# IO_BOTTOM_PCB_BOARD.net
KiCad netlist of a schematic drawn in EAGLE
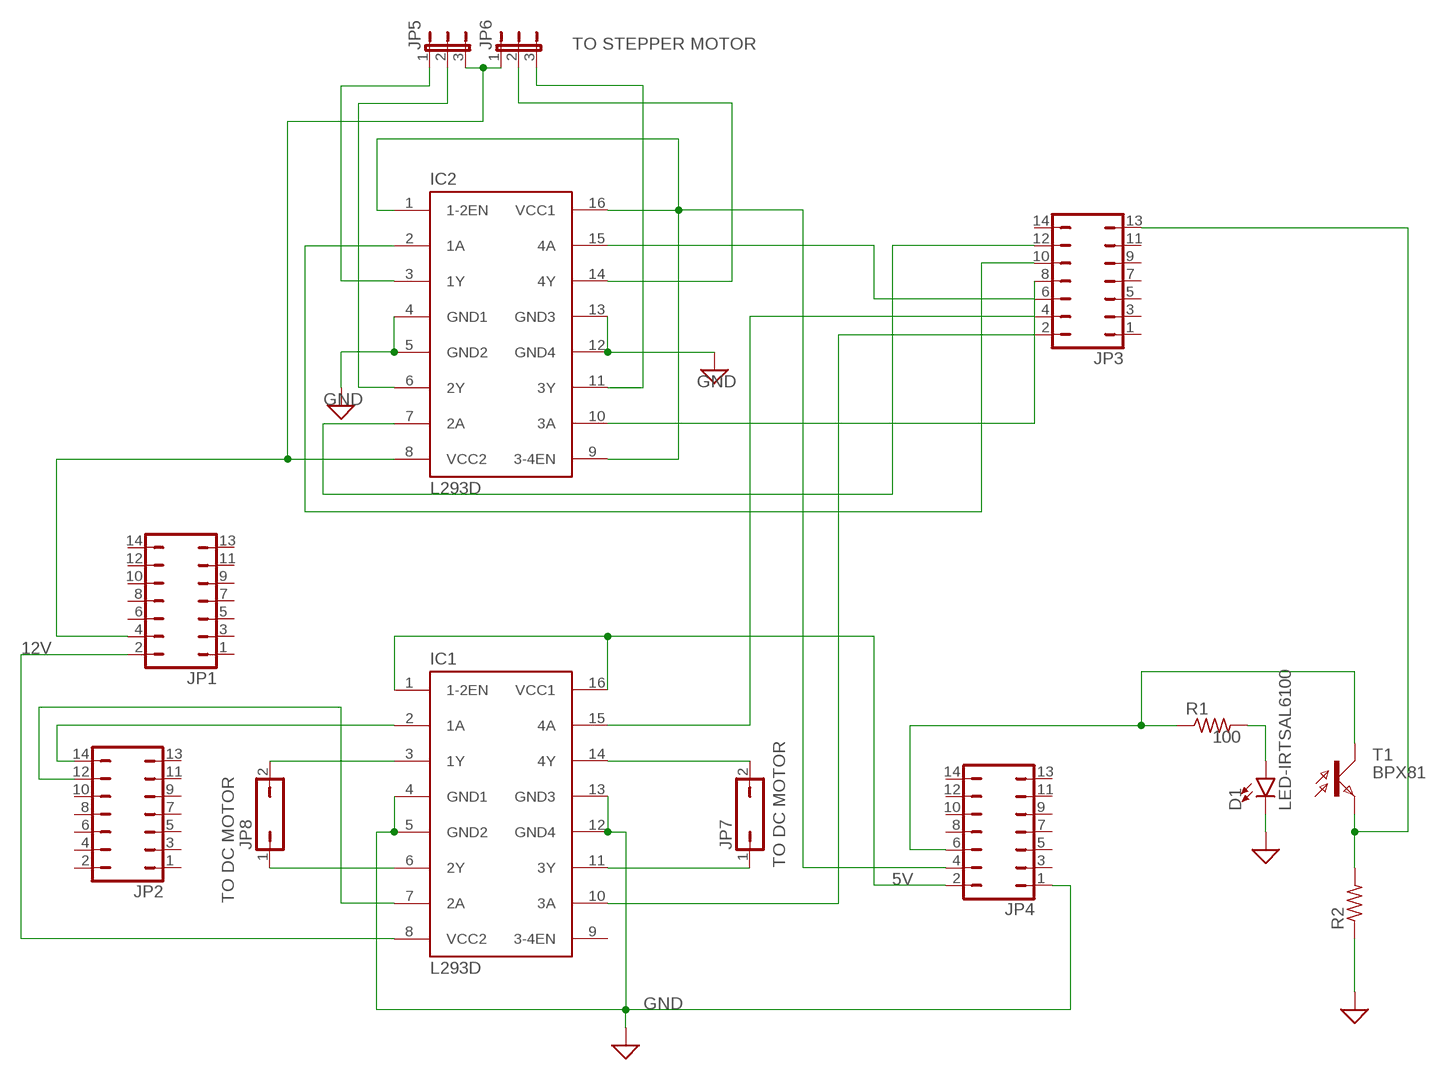
[diagram p0: schematic, sheet 1]

(export (version "E")
  (design (tool "Eeschema 10.0.6"))
  (components
    (comp (ref "D1")
      (value "LED-IRTSAL6100")
      (footprint "eagle-import:LED_5MM")
      (libsource (lib "eagle-import") (part "LED-IRTSAL6100"))
    )
    (comp (ref "IC1")
      (value "L293D")
      (footprint "eagle-import:DIL16")
      (libsource (lib "eagle-import") (part "L293D"))
    )
    (comp (ref "IC2")
      (value "L293D")
      (footprint "eagle-import:DIL16")
      (libsource (lib "eagle-import") (part "L293D"))
    )
    (comp (ref "JP1")
      (value "JP7Q")
      (footprint "eagle-import:JP7Q")
      (libsource (lib "eagle-import") (part "JP7Q"))
    )
    (comp (ref "JP2")
      (value "JP7Q")
      (footprint "eagle-import:JP7Q")
      (libsource (lib "eagle-import") (part "JP7Q"))
    )
    (comp (ref "JP3")
      (value "JP7Q")
      (footprint "eagle-import:JP7Q")
      (libsource (lib "eagle-import") (part "JP7Q"))
    )
    (comp (ref "JP4")
      (value "JP7Q")
      (footprint "eagle-import:JP7Q")
      (libsource (lib "eagle-import") (part "JP7Q"))
    )
    (comp (ref "JP5")
      (value "JP2E")
      (footprint "eagle-import:JP2")
      (libsource (lib "eagle-import") (part "JP2E"))
    )
    (comp (ref "JP6")
      (value "JP2E")
      (footprint "eagle-import:JP2")
      (libsource (lib "eagle-import") (part "JP2E"))
    )
    (comp (ref "JP7")
      (value "JP1Q")
      (footprint "eagle-import:JP1")
      (libsource (lib "eagle-import") (part "JP1Q"))
    )
    (comp (ref "JP8")
      (value "JP1Q")
      (footprint "eagle-import:JP1")
      (libsource (lib "eagle-import") (part "JP1Q"))
    )
    (comp (ref "R1")
      (value "R-US_0204/2V")
      (footprint "eagle-import:0204V")
      (libsource (lib "eagle-import") (part "R-US_0204/2V"))
    )
    (comp (ref "R2")
      (value "R-US_0204/2V")
      (footprint "eagle-import:0204V")
      (libsource (lib "eagle-import") (part "R-US_0204/2V"))
    )
    (comp (ref "T1")
      (value "BPX81")
      (footprint "eagle-import:BPX81")
      (libsource (lib "eagle-import") (part "BPX81"))
    )
  )
  (nets
    (net (code "1") (name "/5V") (class "Default")
      (node (ref "IC1") (pin "8") (pinfunction "VCC2_8") (pintype "power_in"))
      (node (ref "JP1") (pin "2") (pinfunction "2_2") (pintype "passive"))
    )
    (net (code "2") (name "Net-(D1-PadA)") (class "Default")
      (node (ref "D1") (pin "A") (pinfunction "A_A") (pintype "passive"))
      (node (ref "R1") (pin "2") (pinfunction "2_2") (pintype "passive"))
    )
    (net (code "3") (name "Net-(IC1-1-2EN)") (class "Default")
      (node (ref "IC1") (pin "1") (pinfunction "1-2EN_1") (pintype "input"))
      (node (ref "IC1") (pin "16") (pinfunction "VCC1_16") (pintype "power_in"))
      (node (ref "JP4") (pin "2") (pinfunction "2_2") (pintype "passive"))
    )
    (net (code "4") (name "Net-(IC1-1A)") (class "Default")
      (node (ref "IC1") (pin "2") (pinfunction "1A_2") (pintype "input"))
      (node (ref "JP2") (pin "14") (pinfunction "14_14") (pintype "passive"))
    )
    (net (code "5") (name "Net-(IC1-1Y)") (class "Default")
      (node (ref "IC1") (pin "3") (pinfunction "1Y_3") (pintype "output"))
      (node (ref "JP8") (pin "2") (pinfunction "2_2") (pintype "passive"))
    )
    (net (code "6") (name "Net-(IC1-2A)") (class "Default")
      (node (ref "IC1") (pin "7") (pinfunction "2A_7") (pintype "input"))
      (node (ref "JP2") (pin "12") (pinfunction "12_12") (pintype "passive"))
    )
    (net (code "7") (name "Net-(IC1-2Y)") (class "Default")
      (node (ref "IC1") (pin "6") (pinfunction "2Y_6") (pintype "output"))
      (node (ref "JP8") (pin "1") (pinfunction "1_1") (pintype "passive"))
    )
    (net (code "8") (name "Net-(IC1-3A)") (class "Default")
      (node (ref "IC1") (pin "10") (pinfunction "3A_10") (pintype "input"))
      (node (ref "JP3") (pin "2") (pinfunction "2_2") (pintype "passive"))
    )
    (net (code "9") (name "Net-(IC1-3Y)") (class "Default")
      (node (ref "IC1") (pin "11") (pinfunction "3Y_11") (pintype "output"))
      (node (ref "JP7") (pin "1") (pinfunction "1_1") (pintype "passive"))
    )
    (net (code "10") (name "Net-(IC1-4A)") (class "Default")
      (node (ref "IC1") (pin "15") (pinfunction "4A_15") (pintype "input"))
      (node (ref "JP3") (pin "4") (pinfunction "4_4") (pintype "passive"))
    )
    (net (code "11") (name "Net-(IC1-4Y)") (class "Default")
      (node (ref "IC1") (pin "14") (pinfunction "4Y_14") (pintype "output"))
      (node (ref "JP7") (pin "2") (pinfunction "2_2") (pintype "passive"))
    )
    (net (code "12") (name "Net-(IC2-1-2EN)") (class "Default")
      (node (ref "IC2") (pin "1") (pinfunction "1-2EN_1") (pintype "input"))
      (node (ref "IC2") (pin "16") (pinfunction "VCC1_16") (pintype "power_in"))
      (node (ref "IC2") (pin "9") (pinfunction "3-4EN_9") (pintype "input"))
      (node (ref "JP4") (pin "4") (pinfunction "4_4") (pintype "passive"))
    )
    (net (code "13") (name "Net-(IC2-1A)") (class "Default")
      (node (ref "IC2") (pin "2") (pinfunction "1A_2") (pintype "input"))
      (node (ref "JP3") (pin "10") (pinfunction "10_10") (pintype "passive"))
    )
    (net (code "14") (name "Net-(IC2-1Y)") (class "Default")
      (node (ref "IC2") (pin "3") (pinfunction "1Y_3") (pintype "output"))
      (node (ref "JP5") (pin "1") (pinfunction "1_1") (pintype "passive"))
    )
    (net (code "15") (name "Net-(IC2-2A)") (class "Default")
      (node (ref "IC2") (pin "7") (pinfunction "2A_7") (pintype "input"))
      (node (ref "JP3") (pin "12") (pinfunction "12_12") (pintype "passive"))
    )
    (net (code "16") (name "Net-(IC2-2Y)") (class "Default")
      (node (ref "IC2") (pin "6") (pinfunction "2Y_6") (pintype "output"))
      (node (ref "JP5") (pin "2") (pinfunction "2_2") (pintype "passive"))
    )
    (net (code "17") (name "Net-(IC2-3A)") (class "Default")
      (node (ref "IC2") (pin "10") (pinfunction "3A_10") (pintype "input"))
      (node (ref "JP3") (pin "8") (pinfunction "8_8") (pintype "passive"))
    )
    (net (code "18") (name "Net-(IC2-3Y)") (class "Default")
      (node (ref "IC2") (pin "11") (pinfunction "3Y_11") (pintype "output"))
      (node (ref "JP6") (pin "3") (pinfunction "3_3") (pintype "passive"))
    )
    (net (code "19") (name "Net-(IC2-4A)") (class "Default")
      (node (ref "IC2") (pin "15") (pinfunction "4A_15") (pintype "input"))
      (node (ref "JP3") (pin "6") (pinfunction "6_6") (pintype "passive"))
    )
    (net (code "20") (name "Net-(IC2-4Y)") (class "Default")
      (node (ref "IC2") (pin "14") (pinfunction "4Y_14") (pintype "output"))
      (node (ref "JP6") (pin "2") (pinfunction "2_2") (pintype "passive"))
    )
    (net (code "21") (name "Net-(IC2-VCC2)") (class "Default")
      (node (ref "IC2") (pin "8") (pinfunction "VCC2_8") (pintype "power_in"))
      (node (ref "JP1") (pin "4") (pinfunction "4_4") (pintype "passive"))
      (node (ref "JP5") (pin "3") (pinfunction "3_3") (pintype "passive"))
      (node (ref "JP6") (pin "1") (pinfunction "1_1") (pintype "passive"))
    )
    (net (code "22") (name "Net-(JP3-Pad13)") (class "Default")
      (node (ref "JP3") (pin "13") (pinfunction "13_13") (pintype "passive"))
      (node (ref "R2") (pin "2") (pinfunction "2_2") (pintype "passive"))
      (node (ref "T1") (pin "E") (pinfunction "E_E") (pintype "passive"))
    )
    (net (code "23") (name "Net-(JP4-Pad6)") (class "Default")
      (node (ref "JP4") (pin "6") (pinfunction "6_6") (pintype "passive"))
      (node (ref "R1") (pin "1") (pinfunction "1_1") (pintype "passive"))
      (node (ref "T1") (pin "C") (pinfunction "C_C") (pintype "passive"))
    )
    (net (code "24") (name "SUP") (class "Default")
      (node (ref "D1") (pin "K") (pinfunction "C_K") (pintype "passive"))
      (node (ref "IC1") (pin "12") (pinfunction "GND4_12") (pintype "power_in"))
      (node (ref "IC1") (pin "13") (pinfunction "GND3_13") (pintype "power_in"))
      (node (ref "IC1") (pin "4") (pinfunction "GND1_4") (pintype "power_in"))
      (node (ref "IC1") (pin "5") (pinfunction "GND2_5") (pintype "power_in"))
      (node (ref "IC2") (pin "12") (pinfunction "GND4_12") (pintype "power_in"))
      (node (ref "IC2") (pin "13") (pinfunction "GND3_13") (pintype "power_in"))
      (node (ref "IC2") (pin "4") (pinfunction "GND1_4") (pintype "power_in"))
      (node (ref "IC2") (pin "5") (pinfunction "GND2_5") (pintype "power_in"))
      (node (ref "JP4") (pin "1") (pinfunction "1_1") (pintype "passive"))
      (node (ref "R2") (pin "1") (pinfunction "1_1") (pintype "passive"))
    )
    (net (code "25") (name "unconnected-(IC1-3-4EN-Pad9)") (class "Default")
      (node (ref "IC1") (pin "9") (pinfunction "3-4EN_9") (pintype "input"))
    )
    (net (code "26") (name "unconnected-(JP1-Pad1)") (class "Default")
      (node (ref "JP1") (pin "1") (pinfunction "1_1") (pintype "passive"))
    )
    (net (code "27") (name "unconnected-(JP1-Pad3)") (class "Default")
      (node (ref "JP1") (pin "3") (pinfunction "3_3") (pintype "passive"))
    )
    (net (code "28") (name "unconnected-(JP1-Pad5)") (class "Default")
      (node (ref "JP1") (pin "5") (pinfunction "5_5") (pintype "passive"))
    )
    (net (code "29") (name "unconnected-(JP1-Pad6)") (class "Default")
      (node (ref "JP1") (pin "6") (pinfunction "6_6") (pintype "passive"))
    )
    (net (code "30") (name "unconnected-(JP1-Pad7)") (class "Default")
      (node (ref "JP1") (pin "7") (pinfunction "7_7") (pintype "passive"))
    )
    (net (code "31") (name "unconnected-(JP1-Pad8)") (class "Default")
      (node (ref "JP1") (pin "8") (pinfunction "8_8") (pintype "passive"))
    )
    (net (code "32") (name "unconnected-(JP1-Pad9)") (class "Default")
      (node (ref "JP1") (pin "9") (pinfunction "9_9") (pintype "passive"))
    )
    (net (code "33") (name "unconnected-(JP1-Pad10)") (class "Default")
      (node (ref "JP1") (pin "10") (pinfunction "10_10") (pintype "passive"))
    )
    (net (code "34") (name "unconnected-(JP1-Pad11)") (class "Default")
      (node (ref "JP1") (pin "11") (pinfunction "11_11") (pintype "passive"))
    )
    (net (code "35") (name "unconnected-(JP1-Pad12)") (class "Default")
      (node (ref "JP1") (pin "12") (pinfunction "12_12") (pintype "passive"))
    )
    (net (code "36") (name "unconnected-(JP1-Pad13)") (class "Default")
      (node (ref "JP1") (pin "13") (pinfunction "13_13") (pintype "passive"))
    )
    (net (code "37") (name "unconnected-(JP1-Pad14)") (class "Default")
      (node (ref "JP1") (pin "14") (pinfunction "14_14") (pintype "passive"))
    )
    (net (code "38") (name "unconnected-(JP2-Pad1)") (class "Default")
      (node (ref "JP2") (pin "1") (pinfunction "1_1") (pintype "passive"))
    )
    (net (code "39") (name "unconnected-(JP2-Pad2)") (class "Default")
      (node (ref "JP2") (pin "2") (pinfunction "2_2") (pintype "passive"))
    )
    (net (code "40") (name "unconnected-(JP2-Pad3)") (class "Default")
      (node (ref "JP2") (pin "3") (pinfunction "3_3") (pintype "passive"))
    )
    (net (code "41") (name "unconnected-(JP2-Pad4)") (class "Default")
      (node (ref "JP2") (pin "4") (pinfunction "4_4") (pintype "passive"))
    )
    (net (code "42") (name "unconnected-(JP2-Pad5)") (class "Default")
      (node (ref "JP2") (pin "5") (pinfunction "5_5") (pintype "passive"))
    )
    (net (code "43") (name "unconnected-(JP2-Pad6)") (class "Default")
      (node (ref "JP2") (pin "6") (pinfunction "6_6") (pintype "passive"))
    )
    (net (code "44") (name "unconnected-(JP2-Pad7)") (class "Default")
      (node (ref "JP2") (pin "7") (pinfunction "7_7") (pintype "passive"))
    )
    (net (code "45") (name "unconnected-(JP2-Pad8)") (class "Default")
      (node (ref "JP2") (pin "8") (pinfunction "8_8") (pintype "passive"))
    )
    (net (code "46") (name "unconnected-(JP2-Pad9)") (class "Default")
      (node (ref "JP2") (pin "9") (pinfunction "9_9") (pintype "passive"))
    )
    (net (code "47") (name "unconnected-(JP2-Pad10)") (class "Default")
      (node (ref "JP2") (pin "10") (pinfunction "10_10") (pintype "passive"))
    )
    (net (code "48") (name "unconnected-(JP2-Pad11)") (class "Default")
      (node (ref "JP2") (pin "11") (pinfunction "11_11") (pintype "passive"))
    )
    (net (code "49") (name "unconnected-(JP2-Pad13)") (class "Default")
      (node (ref "JP2") (pin "13") (pinfunction "13_13") (pintype "passive"))
    )
    (net (code "50") (name "unconnected-(JP3-Pad1)") (class "Default")
      (node (ref "JP3") (pin "1") (pinfunction "1_1") (pintype "passive"))
    )
    (net (code "51") (name "unconnected-(JP3-Pad3)") (class "Default")
      (node (ref "JP3") (pin "3") (pinfunction "3_3") (pintype "passive"))
    )
    (net (code "52") (name "unconnected-(JP3-Pad5)") (class "Default")
      (node (ref "JP3") (pin "5") (pinfunction "5_5") (pintype "passive"))
    )
    (net (code "53") (name "unconnected-(JP3-Pad7)") (class "Default")
      (node (ref "JP3") (pin "7") (pinfunction "7_7") (pintype "passive"))
    )
    (net (code "54") (name "unconnected-(JP3-Pad9)") (class "Default")
      (node (ref "JP3") (pin "9") (pinfunction "9_9") (pintype "passive"))
    )
    (net (code "55") (name "unconnected-(JP3-Pad11)") (class "Default")
      (node (ref "JP3") (pin "11") (pinfunction "11_11") (pintype "passive"))
    )
    (net (code "56") (name "unconnected-(JP3-Pad14)") (class "Default")
      (node (ref "JP3") (pin "14") (pinfunction "14_14") (pintype "passive"))
    )
    (net (code "57") (name "unconnected-(JP4-Pad3)") (class "Default")
      (node (ref "JP4") (pin "3") (pinfunction "3_3") (pintype "passive"))
    )
    (net (code "58") (name "unconnected-(JP4-Pad5)") (class "Default")
      (node (ref "JP4") (pin "5") (pinfunction "5_5") (pintype "passive"))
    )
    (net (code "59") (name "unconnected-(JP4-Pad7)") (class "Default")
      (node (ref "JP4") (pin "7") (pinfunction "7_7") (pintype "passive"))
    )
    (net (code "60") (name "unconnected-(JP4-Pad8)") (class "Default")
      (node (ref "JP4") (pin "8") (pinfunction "8_8") (pintype "passive"))
    )
    (net (code "61") (name "unconnected-(JP4-Pad9)") (class "Default")
      (node (ref "JP4") (pin "9") (pinfunction "9_9") (pintype "passive"))
    )
    (net (code "62") (name "unconnected-(JP4-Pad10)") (class "Default")
      (node (ref "JP4") (pin "10") (pinfunction "10_10") (pintype "passive"))
    )
    (net (code "63") (name "unconnected-(JP4-Pad11)") (class "Default")
      (node (ref "JP4") (pin "11") (pinfunction "11_11") (pintype "passive"))
    )
    (net (code "64") (name "unconnected-(JP4-Pad12)") (class "Default")
      (node (ref "JP4") (pin "12") (pinfunction "12_12") (pintype "passive"))
    )
    (net (code "65") (name "unconnected-(JP4-Pad13)") (class "Default")
      (node (ref "JP4") (pin "13") (pinfunction "13_13") (pintype "passive"))
    )
    (net (code "66") (name "unconnected-(JP4-Pad14)") (class "Default")
      (node (ref "JP4") (pin "14") (pinfunction "14_14") (pintype "passive"))
    )
  )
)
